# neodk_v1_3.net
KiCad netlist of a schematic drawn in EAGLE
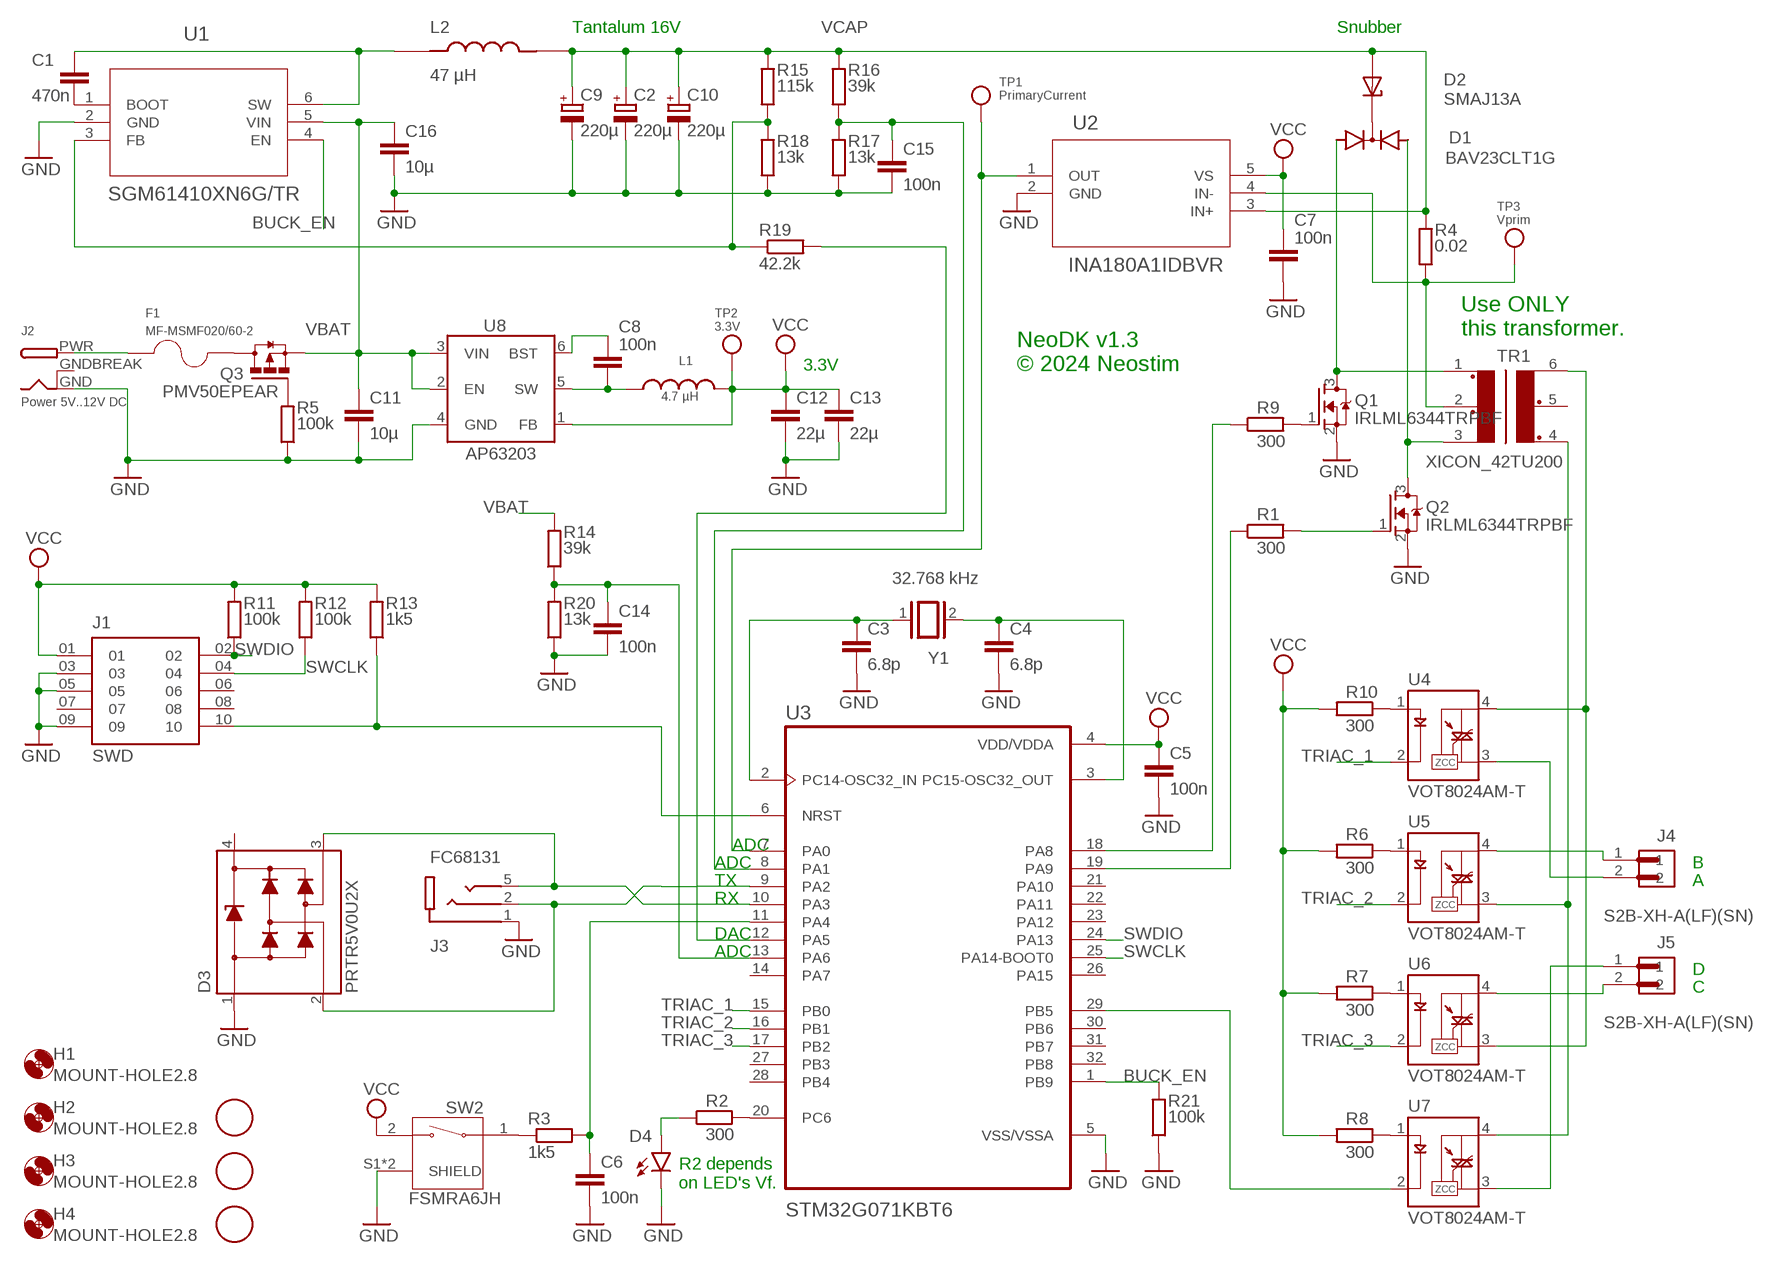
[diagram p0: schematic, sheet 1]

(export (version "E")
  (design (tool "Eeschema 10.0.6"))
  (components
    (comp (ref "C1")
      (value "470n")
      (footprint "eagle-import:C0603")
      (libsource (lib "eagle-import") (part "C-EUC0603"))
    )
    (comp (ref "C2")
      (value "220µ")
      (footprint "eagle-import:SMC_D")
      (fields (field (name "MP") "TPSE227M016R0150"))
      (libsource (lib "eagle-import") (part "CPOL-EUSMCD"))
    )
    (comp (ref "C3")
      (value "6.8p")
      (footprint "eagle-import:C0603")
      (libsource (lib "eagle-import") (part "C-EUC0603"))
    )
    (comp (ref "C4")
      (value "6.8p")
      (footprint "eagle-import:C0603")
      (libsource (lib "eagle-import") (part "C-EUC0603"))
    )
    (comp (ref "C5")
      (value "100n")
      (footprint "eagle-import:C0603")
      (libsource (lib "eagle-import") (part "C-EUC0603"))
    )
    (comp (ref "C6")
      (value "100n")
      (footprint "eagle-import:C0603")
      (libsource (lib "eagle-import") (part "C-EUC0603"))
    )
    (comp (ref "C7")
      (value "100n")
      (footprint "eagle-import:C0603")
      (libsource (lib "eagle-import") (part "C-EUC0603"))
    )
    (comp (ref "C8")
      (value "100n")
      (footprint "eagle-import:C0603")
      (libsource (lib "eagle-import") (part "C-EUC0603"))
    )
    (comp (ref "C9")
      (value "220µ")
      (footprint "eagle-import:SMC_D")
      (fields (field (name "MP") "TPSE227M016R0150"))
      (libsource (lib "eagle-import") (part "CPOL-EUSMCD"))
    )
    (comp (ref "C10")
      (value "220µ")
      (footprint "eagle-import:SMC_D")
      (fields (field (name "MP") "TPSE227M016R0150"))
      (libsource (lib "eagle-import") (part "CPOL-EUSMCD"))
    )
    (comp (ref "C11")
      (value "10µ")
      (footprint "eagle-import:C0603")
      (libsource (lib "eagle-import") (part "C-EUC0603"))
    )
    (comp (ref "C12")
      (value "22µ")
      (footprint "eagle-import:C0603")
      (libsource (lib "eagle-import") (part "C-EUC0603"))
    )
    (comp (ref "C13")
      (value "22µ")
      (footprint "eagle-import:C0603")
      (libsource (lib "eagle-import") (part "C-EUC0603"))
    )
    (comp (ref "C14")
      (value "100n")
      (footprint "eagle-import:C0603")
      (libsource (lib "eagle-import") (part "C-EUC0603"))
    )
    (comp (ref "C15")
      (value "100n")
      (footprint "eagle-import:C0603")
      (libsource (lib "eagle-import") (part "C-EUC0603"))
    )
    (comp (ref "C16")
      (value "10µ")
      (footprint "eagle-import:C0603")
      (libsource (lib "eagle-import") (part "C-EUC0603"))
    )
    (comp (ref "D1")
      (value "BAV23CLT1G")
      (footprint "eagle-import:SOT23")
      (libsource (lib "eagle-import") (part "DIODE-2AC|CASOT23"))
    )
    (comp (ref "D2")
      (value "SMAJ13A")
      (footprint "eagle-import:DIOM4325X250N")
      (fields (field (name "MF") "STMicroelectronics") (field (name "MP") "SMAJ13A-TR"))
      (libsource (lib "eagle-import") (part "SMAJ13A"))
    )
    (comp (ref "D3")
      (value "PRTR5V0U2X")
      (footprint "eagle-import:SOT190P230X110-4N")
      (fields (field (name "MF") "Nexperia USA"))
      (libsource (lib "eagle-import") (part "PRTR5V0U2X"))
    )
    (comp (ref "D4")
      (value "LEDCHIP-LED0805")
      (footprint "eagle-import:CHIP-LED0805")
      (libsource (lib "eagle-import") (part "LEDCHIP-LED0805"))
    )
    (comp (ref "F1")
      (value "MF-MSMF020/60-2")
      (footprint "eagle-import:FUSER_MF-MSMF020_60-2")
      (fields (field (name "MF") "Bourns"))
      (libsource (lib "eagle-import") (part "MF-MSMF020/60-2"))
    )
    (comp (ref "FID1")
      (value "FIDUCIAL")
      (footprint "eagle-import:FIDUCIAL_1MM")
      (libsource (lib "eagle-import") (part "FIDUCIAL"))
    )
    (comp (ref "FID2")
      (value "FIDUCIAL")
      (footprint "eagle-import:FIDUCIAL_1MM")
      (libsource (lib "eagle-import") (part "FIDUCIAL"))
    )
    (comp (ref "FID3")
      (value "FIDUCIAL")
      (footprint "eagle-import:FIDUCIAL_1MM")
      (libsource (lib "eagle-import") (part "FIDUCIAL"))
    )
    (comp (ref "H1")
      (value "MOUNT-HOLE2.8")
      (footprint "eagle-import:2,8")
      (libsource (lib "eagle-import") (part "MOUNT-HOLE2.8"))
    )
    (comp (ref "H2")
      (value "MOUNT-HOLE2.8")
      (footprint "eagle-import:2,8")
      (libsource (lib "eagle-import") (part "MOUNT-HOLE2.8"))
    )
    (comp (ref "H3")
      (value "MOUNT-HOLE2.8")
      (footprint "eagle-import:2,8")
      (libsource (lib "eagle-import") (part "MOUNT-HOLE2.8"))
    )
    (comp (ref "H4")
      (value "MOUNT-HOLE2.8")
      (footprint "eagle-import:2,8")
      (libsource (lib "eagle-import") (part "MOUNT-HOLE2.8"))
    )
    (comp (ref "J1")
      (value "SWD")
      (footprint "eagle-import:SAMTEC_FTSH-105-XX-X-DV")
      (fields (field (name "MF") "Samtec") (field (name "MP") "FTSH-105-01-L-DV"))
      (libsource (lib "eagle-import") (part "FTSH-105-XX-X-DV"))
    )
    (comp (ref "J2")
      (value "Power 5V..12V DC")
      (footprint "eagle-import:DCJACK_2MM_PTH")
      (libsource (lib "eagle-import") (part "DCBARRELPTH"))
    )
    (comp (ref "J3")
      (value "FC68131")
      (footprint "eagle-import:CLIFF_FC68131")
      (fields (field (name "MF") "Cliff"))
      (libsource (lib "eagle-import") (part "FC68131"))
    )
    (comp (ref "J4")
      (value "S2B-XH-A(LF)(SN)")
      (footprint "eagle-import:JST_S2B-XH-A(LF)(SN)")
      (fields (field (name "MF") "JST Sales"))
      (libsource (lib "eagle-import") (part "S2B-XH-A(LF)(SN)"))
    )
    (comp (ref "J5")
      (value "S2B-XH-A(LF)(SN)")
      (footprint "eagle-import:JST_S2B-XH-A(LF)(SN)")
      (fields (field (name "MF") "JST Sales"))
      (libsource (lib "eagle-import") (part "S2B-XH-A(LF)(SN)"))
    )
    (comp (ref "L1")
      (value "4.7 µH")
      (footprint "eagle-import:IND_VLS5045EX-4R7M")
      (fields (field (name "MF") "TDK") (field (name "MP") "VLS5045EX-4R7M"))
      (libsource (lib "eagle-import") (part "VLS5045EX-4R7M"))
    )
    (comp (ref "L2")
      (value "47 µH")
      (footprint "eagle-import:IND_CLF7045NIT-470M-D")
      (fields (field (name "MF") "TDK") (field (name "MP") "CLF7045NIT-470M-D"))
      (libsource (lib "eagle-import") (part "CLF7045NIT-470M-D"))
    )
    (comp (ref "Q1")
      (value "IRLML6344TRPBF")
      (footprint "eagle-import:SOT23")
      (libsource (lib "eagle-import") (part "MOSFET-NREFLOW"))
    )
    (comp (ref "Q2")
      (value "IRLML6344TRPBF")
      (footprint "eagle-import:SOT23")
      (libsource (lib "eagle-import") (part "MOSFET-NREFLOW"))
    )
    (comp (ref "Q3")
      (value "PMV50EPEAR")
      (footprint "eagle-import:SOT23")
      (libsource (lib "eagle-import") (part "PMV50EPEAR"))
    )
    (comp (ref "R1")
      (value "300")
      (footprint "eagle-import:R0603")
      (libsource (lib "eagle-import") (part "R-EU_R0603"))
    )
    (comp (ref "R2")
      (value "300")
      (footprint "eagle-import:R0603")
      (libsource (lib "eagle-import") (part "R-EU_R0603"))
    )
    (comp (ref "R3")
      (value "1k5")
      (footprint "eagle-import:R0603")
      (libsource (lib "eagle-import") (part "R-EU_R0603"))
    )
    (comp (ref "R4")
      (value "0.02")
      (footprint "eagle-import:R1206")
      (libsource (lib "eagle-import") (part "R-EU_R1206"))
    )
    (comp (ref "R5")
      (value "100k")
      (footprint "eagle-import:R0603")
      (libsource (lib "eagle-import") (part "R-EU_R0603"))
    )
    (comp (ref "R6")
      (value "300")
      (footprint "eagle-import:R0603")
      (libsource (lib "eagle-import") (part "R-EU_R0603"))
    )
    (comp (ref "R7")
      (value "300")
      (footprint "eagle-import:R0603")
      (libsource (lib "eagle-import") (part "R-EU_R0603"))
    )
    (comp (ref "R8")
      (value "300")
      (footprint "eagle-import:R0603")
      (libsource (lib "eagle-import") (part "R-EU_R0603"))
    )
    (comp (ref "R9")
      (value "300")
      (footprint "eagle-import:R0603")
      (libsource (lib "eagle-import") (part "R-EU_R0603"))
    )
    (comp (ref "R10")
      (value "300")
      (footprint "eagle-import:R0603")
      (libsource (lib "eagle-import") (part "R-EU_R0603"))
    )
    (comp (ref "R11")
      (value "100k")
      (footprint "eagle-import:R0603")
      (libsource (lib "eagle-import") (part "R-EU_R0603"))
    )
    (comp (ref "R12")
      (value "100k")
      (footprint "eagle-import:R0603")
      (libsource (lib "eagle-import") (part "R-EU_R0603"))
    )
    (comp (ref "R13")
      (value "1k5")
      (footprint "eagle-import:R0603")
      (libsource (lib "eagle-import") (part "R-EU_R0603"))
    )
    (comp (ref "R14")
      (value "39k")
      (footprint "eagle-import:R0603")
      (libsource (lib "eagle-import") (part "R-EU_R0603"))
    )
    (comp (ref "R15")
      (value "115k")
      (footprint "eagle-import:R0603")
      (libsource (lib "eagle-import") (part "R-EU_R0603"))
    )
    (comp (ref "R16")
      (value "39k")
      (footprint "eagle-import:R0603")
      (libsource (lib "eagle-import") (part "R-EU_R0603"))
    )
    (comp (ref "R17")
      (value "13k")
      (footprint "eagle-import:R0603")
      (libsource (lib "eagle-import") (part "R-EU_R0603"))
    )
    (comp (ref "R18")
      (value "13k")
      (footprint "eagle-import:R0603")
      (libsource (lib "eagle-import") (part "R-EU_R0603"))
    )
    (comp (ref "R19")
      (value "42.2k")
      (footprint "eagle-import:R0603")
      (libsource (lib "eagle-import") (part "R-EU_R0603"))
    )
    (comp (ref "R20")
      (value "13k")
      (footprint "eagle-import:R0603")
      (libsource (lib "eagle-import") (part "R-EU_R0603"))
    )
    (comp (ref "R21")
      (value "100k")
      (footprint "eagle-import:R0603")
      (libsource (lib "eagle-import") (part "R-EU_R0603"))
    )
    (comp (ref "SW2")
      (value "FSMRA6JH")
      (footprint "eagle-import:TE_FSMRA6JH")
      (fields (field (name "MF") "TE Connectivity"))
      (libsource (lib "eagle-import") (part "FSMRA6JH"))
    )
    (comp (ref "TP1")
      (value "PrimaryCurrent")
      (footprint "eagle-import:TESTPOINT_ROUND_1MM")
      (libsource (lib "eagle-import") (part "TESTPOINTROUND1MM"))
    )
    (comp (ref "TP2")
      (value "3.3V")
      (footprint "eagle-import:TESTPOINT_ROUND_1MM")
      (libsource (lib "eagle-import") (part "TESTPOINTROUND1MM"))
    )
    (comp (ref "TP3")
      (value "Vprim")
      (footprint "eagle-import:TESTPOINT_ROUND_1MM")
      (libsource (lib "eagle-import") (part "TESTPOINTROUND1MM"))
    )
    (comp (ref "TR1")
      (value "XICON_42TU200")
      (footprint "eagle-import:42TUXXX")
      (libsource (lib "eagle-import") (part "XICON_42TU200"))
    )
    (comp (ref "U1")
      (value "SGM61410XN6G/TR")
      (footprint "eagle-import:SOT-23-6_SNC")
      (libsource (lib "eagle-import") (part "SGM61410XN6G/TR"))
    )
    (comp (ref "U2")
      (value "INA180A1IDBVR")
      (footprint "eagle-import:DBV5")
      (libsource (lib "eagle-import") (part "INA180A1IDBVR"))
    )
    (comp (ref "U3")
      (value "STM32G071KBT6")
      (footprint "eagle-import:QFP80P900X900X160-32N")
      (fields (field (name "MF") "STMicroelectronics") (field (name "MP") "STM32G070KBT6"))
      (libsource (lib "eagle-import") (part "STM32G071KBT6"))
    )
    (comp (ref "U4")
      (value "VOT8024AM-T")
      (footprint "eagle-import:SOP254P675X240-4N")
      (fields (field (name "MF") "Vishay Semiconductor Opto Division"))
      (libsource (lib "eagle-import") (part "VOT8024AM-T"))
    )
    (comp (ref "U5")
      (value "VOT8024AM-T")
      (footprint "eagle-import:SOP254P675X240-4N")
      (fields (field (name "MF") "Vishay Semiconductor Opto Division"))
      (libsource (lib "eagle-import") (part "VOT8024AM-T"))
    )
    (comp (ref "U6")
      (value "VOT8024AM-T")
      (footprint "eagle-import:SOP254P675X240-4N")
      (fields (field (name "MF") "Vishay Semiconductor Opto Division"))
      (libsource (lib "eagle-import") (part "VOT8024AM-T"))
    )
    (comp (ref "U7")
      (value "VOT8024AM-T")
      (footprint "eagle-import:SOP254P675X240-4N")
      (fields (field (name "MF") "Vishay Semiconductor Opto Division"))
      (libsource (lib "eagle-import") (part "VOT8024AM-T"))
    )
    (comp (ref "U8")
      (value "AP63203")
      (footprint "eagle-import:SOT23-6")
      (fields (field (name "MF") "Diodes Zetex") (field (name "MP") "AP63203WU-7"))
      (libsource (lib "eagle-import") (part "AP63203"))
    )
    (comp (ref "Y1")
      (value "32.768 kHz")
      (footprint "eagle-import:XTAL_NX3215SA-32.768K-STD-MUA-8")
      (fields (field (name "MF") "NDK America,") (field (name "MP") "NX3215SA-32.768K-STD-MUA-8"))
      (libsource (lib "eagle-import") (part "NX3215SA-32.768K-STD-MUA-8"))
    )
  )
  (nets
    (net (code "1") (name "/BUCK_EN") (class "Default")
      (node (ref "R21") (pin "2") (pinfunction "2_2") (pintype "passive"))
      (node (ref "U1") (pin "4") (pinfunction "EN_4") (pintype "passive"))
      (node (ref "U3") (pin "1") (pinfunction "PB9_1") (pintype "bidirectional"))
    )
    (net (code "2") (name "/GNDBREAK") (class "Default")
      (node (ref "J2") (pin "GNDBREAK") (pinfunction "GNDBREAK_GNDBREAK") (pintype "power_in"))
    )
    (net (code "3") (name "/SWCLK") (class "Default")
      (node (ref "J1") (pin "04") (pinfunction "04_04") (pintype "passive"))
      (node (ref "R12") (pin "1") (pinfunction "1_1") (pintype "passive"))
      (node (ref "U3") (pin "25") (pinfunction "PA14-BOOT0_25") (pintype "bidirectional"))
    )
    (net (code "4") (name "/SWDIO") (class "Default")
      (node (ref "J1") (pin "02") (pinfunction "02_02") (pintype "passive"))
      (node (ref "R11") (pin "1") (pinfunction "1_1") (pintype "passive"))
      (node (ref "U3") (pin "24") (pinfunction "PA13_24") (pintype "bidirectional"))
    )
    (net (code "5") (name "/TRIAC_1") (class "Default")
      (node (ref "U3") (pin "15") (pinfunction "PB0_15") (pintype "bidirectional"))
      (node (ref "U4") (pin "2") (pinfunction "C_2") (pintype "passive"))
    )
    (net (code "6") (name "/TRIAC_2") (class "Default")
      (node (ref "U3") (pin "16") (pinfunction "PB1_16") (pintype "bidirectional"))
      (node (ref "U5") (pin "2") (pinfunction "C_2") (pintype "passive"))
    )
    (net (code "7") (name "/TRIAC_3") (class "Default")
      (node (ref "U3") (pin "17") (pinfunction "PB2_17") (pintype "bidirectional"))
      (node (ref "U6") (pin "2") (pinfunction "C_2") (pintype "passive"))
    )
    (net (code "8") (name "/VBAT") (class "Default")
      (node (ref "C11") (pin "1") (pinfunction "1_1") (pintype "passive"))
      (node (ref "C16") (pin "1") (pinfunction "1_1") (pintype "passive"))
      (node (ref "Q3") (pin "2") (pinfunction "S_2") (pintype "passive"))
      (node (ref "R14") (pin "2") (pinfunction "2_2") (pintype "passive"))
      (node (ref "U1") (pin "5") (pinfunction "VIN_5") (pintype "power_in"))
      (node (ref "U8") (pin "2") (pinfunction "EN_2") (pintype "bidirectional"))
      (node (ref "U8") (pin "3") (pinfunction "VIN_3") (pintype "bidirectional"))
    )
    (net (code "9") (name "/VCAP") (class "Default")
      (node (ref "C10") (pin "+") (pinfunction "+_+") (pintype "passive"))
      (node (ref "C2") (pin "+") (pinfunction "+_+") (pintype "passive"))
      (node (ref "C9") (pin "+") (pinfunction "+_+") (pintype "passive"))
      (node (ref "D2") (pin "A") (pinfunction "A_A") (pintype "passive"))
      (node (ref "L2") (pin "2") (pinfunction "2_2") (pintype "passive"))
      (node (ref "R15") (pin "2") (pinfunction "2_2") (pintype "passive"))
      (node (ref "R16") (pin "2") (pinfunction "2_2") (pintype "passive"))
      (node (ref "R4") (pin "2") (pinfunction "2_2") (pintype "passive"))
      (node (ref "U2") (pin "3") (pinfunction "IN+_3") (pintype "input"))
    )
    (net (code "10") (name "GND") (class "Default")
      (node (ref "C10") (pin "-") (pinfunction "-_-") (pintype "passive"))
      (node (ref "C11") (pin "2") (pinfunction "2_2") (pintype "passive"))
      (node (ref "C12") (pin "2") (pinfunction "2_2") (pintype "passive"))
      (node (ref "C13") (pin "2") (pinfunction "2_2") (pintype "passive"))
      (node (ref "C14") (pin "2") (pinfunction "2_2") (pintype "passive"))
      (node (ref "C15") (pin "2") (pinfunction "2_2") (pintype "passive"))
      (node (ref "C16") (pin "2") (pinfunction "2_2") (pintype "passive"))
      (node (ref "C2") (pin "-") (pinfunction "-_-") (pintype "passive"))
      (node (ref "C3") (pin "2") (pinfunction "2_2") (pintype "passive"))
      (node (ref "C4") (pin "2") (pinfunction "2_2") (pintype "passive"))
      (node (ref "C5") (pin "2") (pinfunction "2_2") (pintype "passive"))
      (node (ref "C6") (pin "2") (pinfunction "2_2") (pintype "passive"))
      (node (ref "C7") (pin "2") (pinfunction "2_2") (pintype "passive"))
      (node (ref "C9") (pin "-") (pinfunction "-_-") (pintype "passive"))
      (node (ref "D3") (pin "1") (pinfunction "GND_1") (pintype "passive"))
      (node (ref "D4") (pin "C") (pinfunction "C_C") (pintype "passive"))
      (node (ref "J1") (pin "03") (pinfunction "03_03") (pintype "passive"))
      (node (ref "J1") (pin "05") (pinfunction "05_05") (pintype "passive"))
      (node (ref "J1") (pin "09") (pinfunction "09_09") (pintype "passive"))
      (node (ref "J2") (pin "GND") (pinfunction "GND_GND") (pintype "power_in"))
      (node (ref "J3") (pin "1") (pinfunction "SLEEVE_1") (pintype "passive"))
      (node (ref "Q1") (pin "2") (pinfunction "S_2") (pintype "bidirectional"))
      (node (ref "Q2") (pin "2") (pinfunction "S_2") (pintype "bidirectional"))
      (node (ref "R17") (pin "1") (pinfunction "1_1") (pintype "passive"))
      (node (ref "R18") (pin "1") (pinfunction "1_1") (pintype "passive"))
      (node (ref "R20") (pin "1") (pinfunction "1_1") (pintype "passive"))
      (node (ref "R21") (pin "1") (pinfunction "1_1") (pintype "passive"))
      (node (ref "R5") (pin "1") (pinfunction "1_1") (pintype "passive"))
      (node (ref "SW2") (pin "S1") (pinfunction "SHIELD_S1") (pintype "passive"))
      (node (ref "SW2") (pin "S2") (pinfunction "SHIELD_S2") (pintype "passive"))
      (node (ref "U1") (pin "2") (pinfunction "GND_2") (pintype "passive"))
      (node (ref "U2") (pin "2") (pinfunction "GND_2") (pintype "power_in"))
      (node (ref "U3") (pin "5") (pinfunction "VSS/VSSA_5") (pintype "power_in"))
      (node (ref "U8") (pin "4") (pinfunction "GND_4") (pintype "bidirectional"))
    )
    (net (code "11") (name "Net-(D1-A1)") (class "Default")
      (node (ref "D1") (pin "1") (pinfunction "A1_1") (pintype "passive"))
      (node (ref "Q1") (pin "3") (pinfunction "D_3") (pintype "bidirectional"))
      (node (ref "TR1") (pin "1") (pinfunction "1_1") (pintype "passive"))
    )
    (net (code "12") (name "Net-(D1-A2)") (class "Default")
      (node (ref "D1") (pin "2") (pinfunction "A2_2") (pintype "passive"))
      (node (ref "Q2") (pin "3") (pinfunction "D_3") (pintype "bidirectional"))
      (node (ref "TR1") (pin "3") (pinfunction "3_3") (pintype "passive"))
    )
    (net (code "13") (name "Net-(D1-C)") (class "Default")
      (node (ref "D1") (pin "3") (pinfunction "C_3") (pintype "passive"))
      (node (ref "D2") (pin "C") (pinfunction "C_C") (pintype "passive"))
    )
    (net (code "14") (name "Net-(D3-I{slash}O_1)") (class "Default")
      (node (ref "D3") (pin "2") (pinfunction "I/O_1_2") (pintype "passive"))
      (node (ref "J3") (pin "2") (pinfunction "RING_2") (pintype "passive"))
      (node (ref "U3") (pin "9") (pinfunction "PA2_9") (pintype "bidirectional"))
    )
    (net (code "15") (name "Net-(D3-I{slash}O_2)") (class "Default")
      (node (ref "D3") (pin "3") (pinfunction "I/O_2_3") (pintype "passive"))
      (node (ref "J3") (pin "5") (pinfunction "TIP_5") (pintype "passive"))
      (node (ref "U3") (pin "10") (pinfunction "PA3_10") (pintype "bidirectional"))
    )
    (net (code "16") (name "Net-(D4-PadA)") (class "Default")
      (node (ref "D4") (pin "A") (pinfunction "A_A") (pintype "passive"))
      (node (ref "R2") (pin "1") (pinfunction "1_1") (pintype "passive"))
    )
    (net (code "17") (name "Net-(F1-Pad1)") (class "Default")
      (node (ref "F1") (pin "1") (pinfunction "1_1") (pintype "passive"))
      (node (ref "J2") (pin "PWR") (pinfunction "PWR_PWR") (pintype "power_in"))
    )
    (net (code "18") (name "Net-(Q1-G)") (class "Default")
      (node (ref "Q1") (pin "1") (pinfunction "G_1") (pintype "bidirectional"))
      (node (ref "R9") (pin "2") (pinfunction "2_2") (pintype "passive"))
    )
    (net (code "19") (name "Net-(Q2-G)") (class "Default")
      (node (ref "Q2") (pin "1") (pinfunction "G_1") (pintype "bidirectional"))
      (node (ref "R1") (pin "2") (pinfunction "2_2") (pintype "passive"))
    )
    (net (code "20") (name "Net-(Q3-D)") (class "Default")
      (node (ref "F1") (pin "2") (pinfunction "2_2") (pintype "passive"))
      (node (ref "Q3") (pin "3") (pinfunction "D_3") (pintype "passive"))
    )
    (net (code "21") (name "Net-(Q3-G)") (class "Default")
      (node (ref "Q3") (pin "1") (pinfunction "G_1") (pintype "passive"))
      (node (ref "R5") (pin "2") (pinfunction "2_2") (pintype "passive"))
    )
    (net (code "22") (name "Net-(R3-Pad1)") (class "Default")
      (node (ref "R3") (pin "1") (pinfunction "1_1") (pintype "passive"))
      (node (ref "SW2") (pin "1") (pinfunction "1_1") (pintype "passive"))
    )
    (net (code "23") (name "Net-(U1-BOOT)") (class "Default")
      (node (ref "C1") (pin "2") (pinfunction "2_2") (pintype "passive"))
      (node (ref "U1") (pin "1") (pinfunction "BOOT_1") (pintype "passive"))
    )
    (net (code "24") (name "Net-(U1-FB)") (class "Default")
      (node (ref "R15") (pin "1") (pinfunction "1_1") (pintype "passive"))
      (node (ref "R18") (pin "2") (pinfunction "2_2") (pintype "passive"))
      (node (ref "R19") (pin "1") (pinfunction "1_1") (pintype "passive"))
      (node (ref "U1") (pin "3") (pinfunction "FB_3") (pintype "passive"))
    )
    (net (code "25") (name "Net-(U1-SW)") (class "Default")
      (node (ref "C1") (pin "1") (pinfunction "1_1") (pintype "passive"))
      (node (ref "L2") (pin "1") (pinfunction "1_1") (pintype "passive"))
      (node (ref "U1") (pin "6") (pinfunction "SW_6") (pintype "output"))
    )
    (net (code "26") (name "Net-(U2-IN-)") (class "Default")
      (node (ref "R4") (pin "1") (pinfunction "1_1") (pintype "passive"))
      (node (ref "TP3") (pin "P$1") (pinfunction "P$1_P$1") (pintype "bidirectional"))
      (node (ref "TR1") (pin "2") (pinfunction "2_2") (pintype "passive"))
      (node (ref "U2") (pin "4") (pinfunction "IN-_4") (pintype "input"))
    )
    (net (code "27") (name "Net-(U2-OUT)") (class "Default")
      (node (ref "TP1") (pin "P$1") (pinfunction "P$1_P$1") (pintype "bidirectional"))
      (node (ref "U2") (pin "1") (pinfunction "OUT_1") (pintype "output"))
      (node (ref "U3") (pin "7") (pinfunction "PA0_7") (pintype "bidirectional"))
    )
    (net (code "28") (name "Net-(U3-NRST)") (class "Default")
      (node (ref "J1") (pin "10") (pinfunction "10_10") (pintype "passive"))
      (node (ref "R13") (pin "1") (pinfunction "1_1") (pintype "passive"))
      (node (ref "U3") (pin "6") (pinfunction "NRST_6") (pintype "bidirectional"))
    )
    (net (code "29") (name "Net-(U3-PA1)") (class "Default")
      (node (ref "C15") (pin "1") (pinfunction "1_1") (pintype "passive"))
      (node (ref "R16") (pin "1") (pinfunction "1_1") (pintype "passive"))
      (node (ref "R17") (pin "2") (pinfunction "2_2") (pintype "passive"))
      (node (ref "U3") (pin "8") (pinfunction "PA1_8") (pintype "bidirectional"))
    )
    (net (code "30") (name "Net-(U3-PA4)") (class "Default")
      (node (ref "C6") (pin "1") (pinfunction "1_1") (pintype "passive"))
      (node (ref "R3") (pin "2") (pinfunction "2_2") (pintype "passive"))
      (node (ref "U3") (pin "11") (pinfunction "PA4_11") (pintype "bidirectional"))
    )
    (net (code "31") (name "Net-(U3-PA5)") (class "Default")
      (node (ref "R19") (pin "2") (pinfunction "2_2") (pintype "passive"))
      (node (ref "U3") (pin "12") (pinfunction "PA5_12") (pintype "bidirectional"))
    )
    (net (code "32") (name "Net-(U3-PA6)") (class "Default")
      (node (ref "C14") (pin "1") (pinfunction "1_1") (pintype "passive"))
      (node (ref "R14") (pin "1") (pinfunction "1_1") (pintype "passive"))
      (node (ref "R20") (pin "2") (pinfunction "2_2") (pintype "passive"))
      (node (ref "U3") (pin "13") (pinfunction "PA6_13") (pintype "bidirectional"))
    )
    (net (code "33") (name "Net-(U3-PA8)") (class "Default")
      (node (ref "R9") (pin "1") (pinfunction "1_1") (pintype "passive"))
      (node (ref "U3") (pin "18") (pinfunction "PA8_18") (pintype "bidirectional"))
    )
    (net (code "34") (name "Net-(U3-PA9)") (class "Default")
      (node (ref "R1") (pin "1") (pinfunction "1_1") (pintype "passive"))
      (node (ref "U3") (pin "19") (pinfunction "PA9_19") (pintype "bidirectional"))
    )
    (net (code "35") (name "Net-(U3-PB5)") (class "Default")
      (node (ref "U3") (pin "29") (pinfunction "PB5_29") (pintype "bidirectional"))
      (node (ref "U7") (pin "2") (pinfunction "C_2") (pintype "passive"))
    )
    (net (code "36") (name "Net-(U3-PC6)") (class "Default")
      (node (ref "R2") (pin "2") (pinfunction "2_2") (pintype "passive"))
      (node (ref "U3") (pin "20") (pinfunction "PC6_20") (pintype "bidirectional"))
    )
    (net (code "37") (name "Net-(U3-PC14-OSC32_IN)") (class "Default")
      (node (ref "C3") (pin "1") (pinfunction "1_1") (pintype "passive"))
      (node (ref "U3") (pin "2") (pinfunction "PC14-OSC32_IN_2") (pintype "input"))
      (node (ref "Y1") (pin "1") (pinfunction "1_1") (pintype "passive"))
    )
    (net (code "38") (name "Net-(U3-PC15-OSC32_OUT)") (class "Default")
      (node (ref "C4") (pin "1") (pinfunction "1_1") (pintype "passive"))
      (node (ref "U3") (pin "3") (pinfunction "PC15-OSC32_OUT_3") (pintype "output"))
      (node (ref "Y1") (pin "2") (pinfunction "2_2") (pintype "passive"))
    )
    (net (code "39") (name "Net-(U4-A)") (class "Default")
      (node (ref "R10") (pin "1") (pinfunction "1_1") (pintype "passive"))
      (node (ref "U4") (pin "1") (pinfunction "A_1") (pintype "passive"))
    )
    (net (code "40") (name "Net-(U4-MT1)") (class "Default")
      (node (ref "J4") (pin "2") (pinfunction "2_2") (pintype "passive"))
      (node (ref "U4") (pin "3") (pinfunction "MT1_3") (pintype "passive"))
    )
    (net (code "41") (name "Net-(U4-MT2)") (class "Default")
      (node (ref "TR1") (pin "6") (pinfunction "6_6") (pintype "passive"))
      (node (ref "U4") (pin "4") (pinfunction "MT2_4") (pintype "passive"))
      (node (ref "U6") (pin "3") (pinfunction "MT1_3") (pintype "passive"))
    )
    (net (code "42") (name "Net-(U5-A)") (class "Default")
      (node (ref "R6") (pin "1") (pinfunction "1_1") (pintype "passive"))
      (node (ref "U5") (pin "1") (pinfunction "A_1") (pintype "passive"))
    )
    (net (code "43") (name "Net-(U5-MT1)") (class "Default")
      (node (ref "TR1") (pin "4") (pinfunction "4_4") (pintype "passive"))
      (node (ref "U5") (pin "3") (pinfunction "MT1_3") (pintype "passive"))
      (node (ref "U7") (pin "4") (pinfunction "MT2_4") (pintype "passive"))
    )
    (net (code "44") (name "Net-(U5-MT2)") (class "Default")
      (node (ref "J4") (pin "1") (pinfunction "1_1") (pintype "passive"))
      (node (ref "U5") (pin "4") (pinfunction "MT2_4") (pintype "passive"))
    )
    (net (code "45") (name "Net-(U6-A)") (class "Default")
      (node (ref "R7") (pin "1") (pinfunction "1_1") (pintype "passive"))
      (node (ref "U6") (pin "1") (pinfunction "A_1") (pintype "passive"))
    )
    (net (code "46") (name "Net-(U6-MT2)") (class "Default")
      (node (ref "J5") (pin "2") (pinfunction "2_2") (pintype "passive"))
      (node (ref "U6") (pin "4") (pinfunction "MT2_4") (pintype "passive"))
    )
    (net (code "47") (name "Net-(U7-A)") (class "Default")
      (node (ref "R8") (pin "1") (pinfunction "1_1") (pintype "passive"))
      (node (ref "U7") (pin "1") (pinfunction "A_1") (pintype "passive"))
    )
    (net (code "48") (name "Net-(U7-MT1)") (class "Default")
      (node (ref "J5") (pin "1") (pinfunction "1_1") (pintype "passive"))
      (node (ref "U7") (pin "3") (pinfunction "MT1_3") (pintype "passive"))
    )
    (net (code "49") (name "Net-(U8-BST)") (class "Default")
      (node (ref "C8") (pin "1") (pinfunction "1_1") (pintype "passive"))
      (node (ref "U8") (pin "6") (pinfunction "BST_6") (pintype "bidirectional"))
    )
    (net (code "50") (name "Net-(U8-SW)") (class "Default")
      (node (ref "C8") (pin "2") (pinfunction "2_2") (pintype "passive"))
      (node (ref "L1") (pin "1") (pinfunction "1_1") (pintype "passive"))
      (node (ref "U8") (pin "5") (pinfunction "SW_5") (pintype "bidirectional"))
    )
    (net (code "51") (name "VCC") (class "Default")
      (node (ref "C12") (pin "1") (pinfunction "1_1") (pintype "passive"))
      (node (ref "C13") (pin "1") (pinfunction "1_1") (pintype "passive"))
      (node (ref "C5") (pin "1") (pinfunction "1_1") (pintype "passive"))
      (node (ref "C7") (pin "1") (pinfunction "1_1") (pintype "passive"))
      (node (ref "J1") (pin "01") (pinfunction "01_01") (pintype "passive"))
      (node (ref "L1") (pin "2") (pinfunction "2_2") (pintype "passive"))
      (node (ref "R10") (pin "2") (pinfunction "2_2") (pintype "passive"))
      (node (ref "R11") (pin "2") (pinfunction "2_2") (pintype "passive"))
      (node (ref "R12") (pin "2") (pinfunction "2_2") (pintype "passive"))
      (node (ref "R13") (pin "2") (pinfunction "2_2") (pintype "passive"))
      (node (ref "R6") (pin "2") (pinfunction "2_2") (pintype "passive"))
      (node (ref "R7") (pin "2") (pinfunction "2_2") (pintype "passive"))
      (node (ref "R8") (pin "2") (pinfunction "2_2") (pintype "passive"))
      (node (ref "SW2") (pin "2") (pinfunction "2_2") (pintype "passive"))
      (node (ref "TP2") (pin "P$1") (pinfunction "P$1_P$1") (pintype "bidirectional"))
      (node (ref "U2") (pin "5") (pinfunction "VS_5") (pintype "power_in"))
      (node (ref "U3") (pin "4") (pinfunction "VDD/VDDA_4") (pintype "power_in"))
      (node (ref "U8") (pin "1") (pinfunction "FB_1") (pintype "bidirectional"))
    )
    (net (code "52") (name "unconnected-(D3-VCC-Pad4)") (class "Default")
      (node (ref "D3") (pin "4") (pinfunction "VCC_4") (pintype "passive"))
    )
    (net (code "53") (name "unconnected-(J1-Pad06)") (class "Default")
      (node (ref "J1") (pin "06") (pinfunction "06_06") (pintype "passive"))
    )
    (net (code "54") (name "unconnected-(J1-Pad07)") (class "Default")
      (node (ref "J1") (pin "07") (pinfunction "07_07") (pintype "passive"))
    )
    (net (code "55") (name "unconnected-(J1-Pad08)") (class "Default")
      (node (ref "J1") (pin "08") (pinfunction "08_08") (pintype "passive"))
    )
    (net (code "56") (name "unconnected-(TR1-Pad5)") (class "Default")
      (node (ref "TR1") (pin "5") (pinfunction "5_5") (pintype "passive"))
    )
    (net (code "57") (name "unconnected-(U3-PA7-Pad14)") (class "Default")
      (node (ref "U3") (pin "14") (pinfunction "PA7_14") (pintype "bidirectional"))
    )
    (net (code "58") (name "unconnected-(U3-PA10-Pad21)") (class "Default")
      (node (ref "U3") (pin "21") (pinfunction "PA10_21") (pintype "bidirectional"))
    )
    (net (code "59") (name "unconnected-(U3-PA11-Pad22)") (class "Default")
      (node (ref "U3") (pin "22") (pinfunction "PA11_22") (pintype "bidirectional"))
    )
    (net (code "60") (name "unconnected-(U3-PA12-Pad23)") (class "Default")
      (node (ref "U3") (pin "23") (pinfunction "PA12_23") (pintype "bidirectional"))
    )
    (net (code "61") (name "unconnected-(U3-PA15-Pad26)") (class "Default")
      (node (ref "U3") (pin "26") (pinfunction "PA15_26") (pintype "bidirectional"))
    )
    (net (code "62") (name "unconnected-(U3-PB3-Pad27)") (class "Default")
      (node (ref "U3") (pin "27") (pinfunction "PB3_27") (pintype "bidirectional"))
    )
    (net (code "63") (name "unconnected-(U3-PB4-Pad28)") (class "Default")
      (node (ref "U3") (pin "28") (pinfunction "PB4_28") (pintype "bidirectional"))
    )
    (net (code "64") (name "unconnected-(U3-PB6-Pad30)") (class "Default")
      (node (ref "U3") (pin "30") (pinfunction "PB6_30") (pintype "bidirectional"))
    )
    (net (code "65") (name "unconnected-(U3-PB7-Pad31)") (class "Default")
      (node (ref "U3") (pin "31") (pinfunction "PB7_31") (pintype "bidirectional"))
    )
    (net (code "66") (name "unconnected-(U3-PB8-Pad32)") (class "Default")
      (node (ref "U3") (pin "32") (pinfunction "PB8_32") (pintype "bidirectional"))
    )
  )
)
